# AVR28ZIF.net
KiCad netlist of a schematic drawn in EAGLE
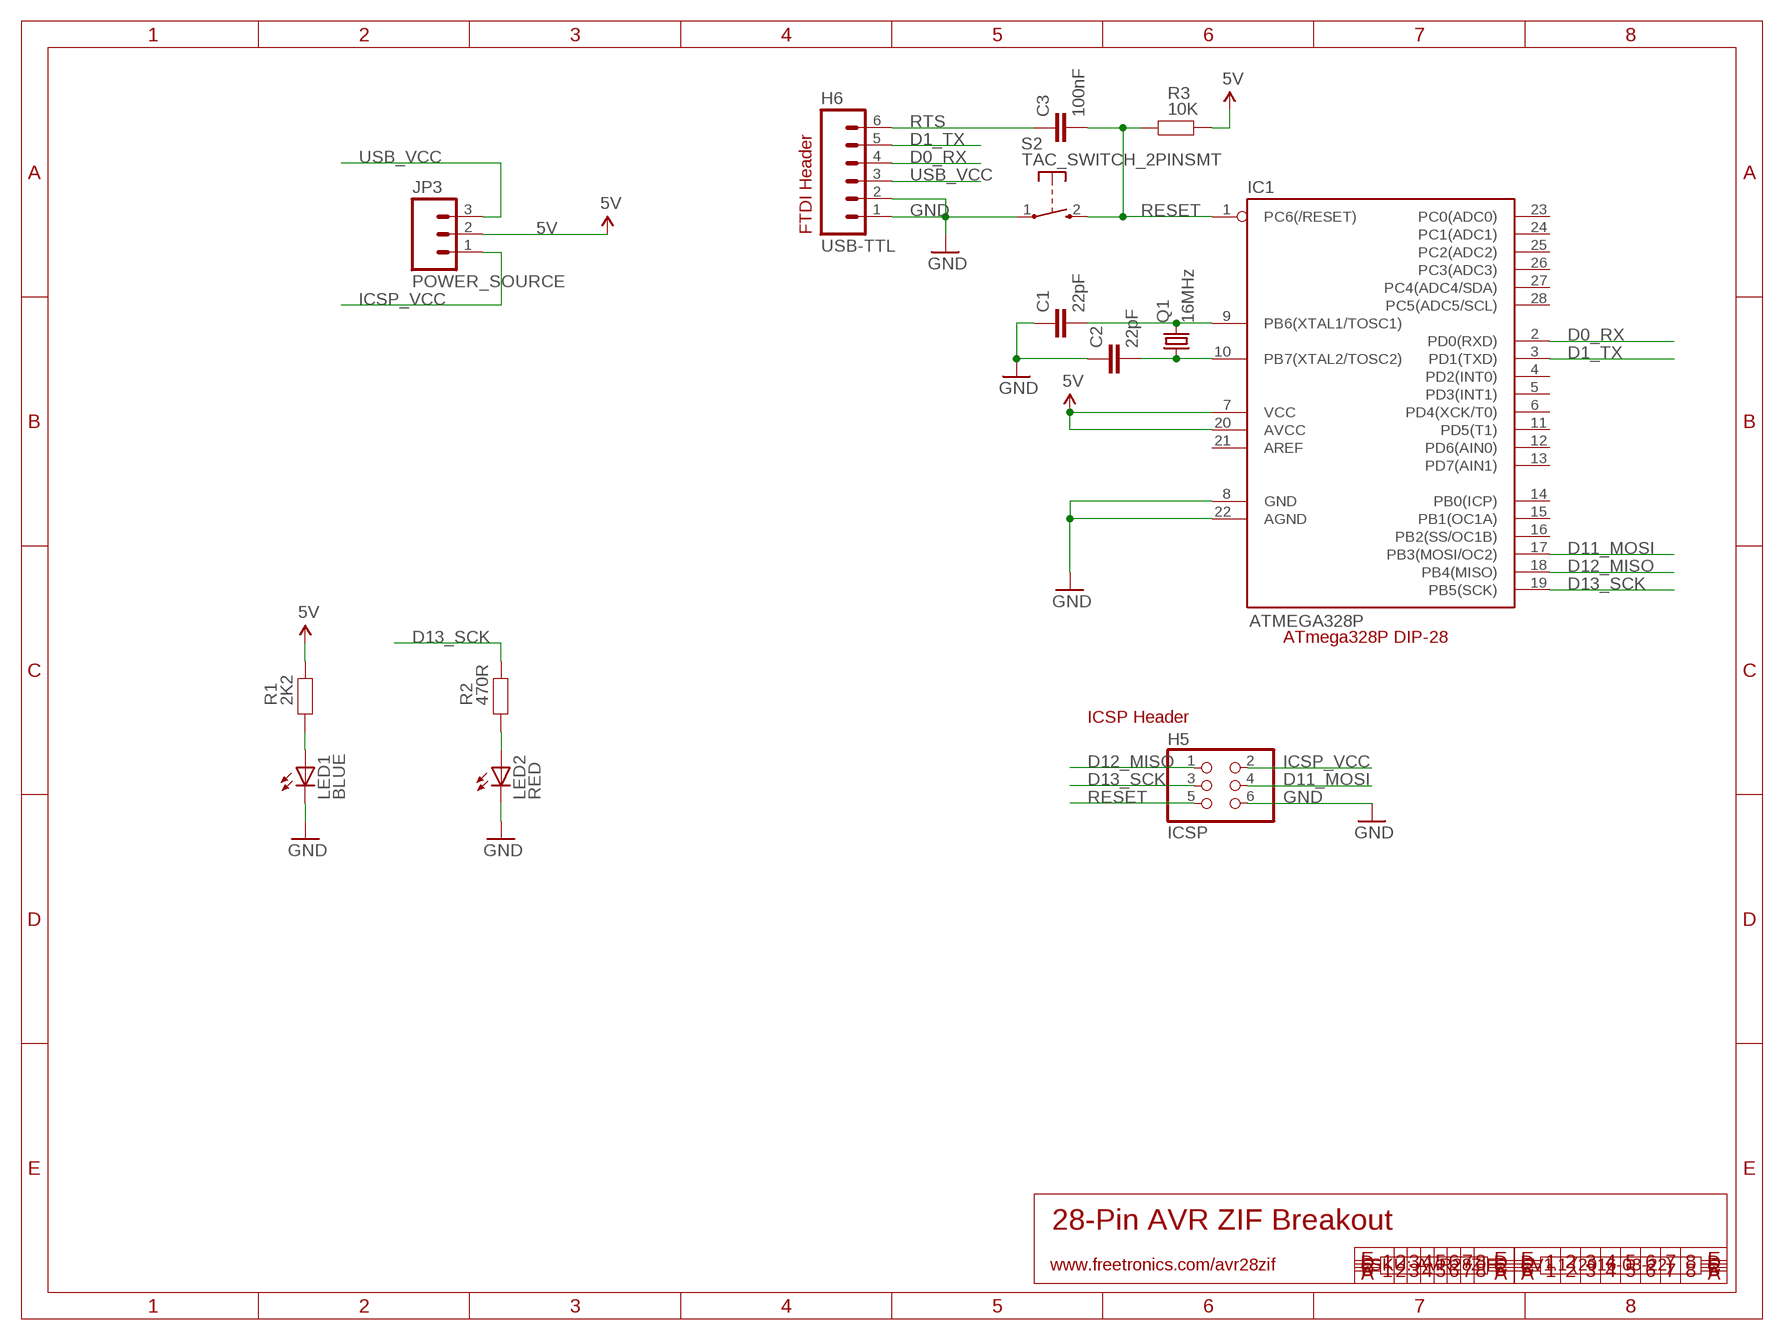
[diagram p0: schematic, sheet 1]

(export (version "E")
  (design (tool "Eeschema 10.0.6"))
  (components
    (comp (ref "C1")
      (value "22pF")
      (footprint "eagle-import:0603")
      (libsource (lib "eagle-import") (part "CAP0603"))
    )
    (comp (ref "C2")
      (value "22pF")
      (footprint "eagle-import:0603")
      (libsource (lib "eagle-import") (part "CAP0603"))
    )
    (comp (ref "C3")
      (value "100nF")
      (footprint "eagle-import:0603")
      (libsource (lib "eagle-import") (part "CAP0603"))
    )
    (comp (ref "H5")
      (value "ICSP")
      (footprint "eagle-import:2X03")
      (libsource (lib "eagle-import") (part "PINHD-2X3"))
    )
    (comp (ref "H6")
      (value "USB-TTL")
      (footprint "eagle-import:1X06")
      (libsource (lib "eagle-import") (part "M06SIP"))
    )
    (comp (ref "IC1")
      (value "ATMEGA328P")
      (footprint "eagle-import:DIL28-3-ZIF")
      (libsource (lib "eagle-import") (part "AVR-MEGA8-PZIF"))
    )
    (comp (ref "JP3")
      (value "POWER_SOURCE")
      (footprint "eagle-import:1X03")
      (libsource (lib "eagle-import") (part "M03PTH"))
    )
    (comp (ref "LED1")
      (value "BLUE")
      (footprint "eagle-import:LED-0603")
      (libsource (lib "eagle-import") (part "LED0603"))
    )
    (comp (ref "LED2")
      (value "RED")
      (footprint "eagle-import:LED-0603")
      (libsource (lib "eagle-import") (part "LED0603"))
    )
    (comp (ref "Q1")
      (value "16MHz")
      (footprint "eagle-import:HC49US")
      (libsource (lib "eagle-import") (part "CRYSTALHC49US"))
    )
    (comp (ref "R1")
      (value "2K2")
      (footprint "eagle-import:0603")
      (libsource (lib "eagle-import") (part "RESISTOR0603"))
    )
    (comp (ref "R2")
      (value "470R")
      (footprint "eagle-import:0603")
      (libsource (lib "eagle-import") (part "RESISTOR0603"))
    )
    (comp (ref "R3")
      (value "10K")
      (footprint "eagle-import:0603")
      (libsource (lib "eagle-import") (part "RESISTOR0603"))
    )
    (comp (ref "S2")
      (value "TAC_SWITCH_2PINSMT")
      (footprint "eagle-import:TACTILE_SWITCH_SMD_2PIN_TINY")
      (libsource (lib "eagle-import") (part "TAC_SWITCH_2PINSMT"))
    )
  )
  (nets
    (net (code "1") (name "/D0_RX") (class "Default")
      (node (ref "H6") (pin "4") (pinfunction "4_4") (pintype "passive"))
      (node (ref "IC1") (pin "2") (pinfunction "PD0(RXD)_2") (pintype "bidirectional"))
    )
    (net (code "2") (name "/D1_TX") (class "Default")
      (node (ref "H6") (pin "5") (pinfunction "5_5") (pintype "passive"))
      (node (ref "IC1") (pin "3") (pinfunction "PD1(TXD)_3") (pintype "bidirectional"))
    )
    (net (code "3") (name "/D11_MOSI") (class "Default")
      (node (ref "H5") (pin "4") (pinfunction "4_4") (pintype "passive"))
      (node (ref "IC1") (pin "17") (pinfunction "PB3(MOSI/OC2)_17") (pintype "bidirectional"))
    )
    (net (code "4") (name "/D12_MISO") (class "Default")
      (node (ref "H5") (pin "1") (pinfunction "1_1") (pintype "passive"))
      (node (ref "IC1") (pin "18") (pinfunction "PB4(MISO)_18") (pintype "bidirectional"))
    )
    (net (code "5") (name "/D13_SCK") (class "Default")
      (node (ref "H5") (pin "3") (pinfunction "3_3") (pintype "passive"))
      (node (ref "IC1") (pin "19") (pinfunction "PB5(SCK)_19") (pintype "bidirectional"))
      (node (ref "R2") (pin "2") (pinfunction "2_2") (pintype "passive"))
    )
    (net (code "6") (name "/ICSP_VCC") (class "Default")
      (node (ref "H5") (pin "2") (pinfunction "2_2") (pintype "passive"))
      (node (ref "JP3") (pin "1") (pinfunction "1_1") (pintype "passive"))
    )
    (net (code "7") (name "/RESET") (class "Default")
      (node (ref "C3") (pin "2") (pinfunction "2_2") (pintype "passive"))
      (node (ref "H5") (pin "5") (pinfunction "5_5") (pintype "passive"))
      (node (ref "IC1") (pin "1") (pinfunction "PC6(/RESET)_1") (pintype "bidirectional"))
      (node (ref "R3") (pin "1") (pinfunction "1_1") (pintype "passive"))
      (node (ref "S2") (pin "2") (pinfunction "S_2") (pintype "passive"))
    )
    (net (code "8") (name "/RTS") (class "Default")
      (node (ref "C3") (pin "1") (pinfunction "1_1") (pintype "passive"))
      (node (ref "H6") (pin "6") (pinfunction "6_6") (pintype "passive"))
    )
    (net (code "9") (name "/USB_VCC") (class "Default")
      (node (ref "H6") (pin "3") (pinfunction "3_3") (pintype "passive"))
      (node (ref "JP3") (pin "3") (pinfunction "3_3") (pintype "passive"))
    )
    (net (code "10") (name "5V") (class "Default")
      (node (ref "IC1") (pin "20") (pinfunction "AVCC_20") (pintype "bidirectional"))
      (node (ref "IC1") (pin "7") (pinfunction "VCC_7") (pintype "bidirectional"))
      (node (ref "JP3") (pin "2") (pinfunction "2_2") (pintype "passive"))
      (node (ref "R1") (pin "2") (pinfunction "2_2") (pintype "passive"))
      (node (ref "R3") (pin "2") (pinfunction "2_2") (pintype "passive"))
    )
    (net (code "11") (name "GND") (class "Default")
      (node (ref "C1") (pin "1") (pinfunction "1_1") (pintype "passive"))
      (node (ref "C2") (pin "1") (pinfunction "1_1") (pintype "passive"))
      (node (ref "H5") (pin "6") (pinfunction "6_6") (pintype "passive"))
      (node (ref "H6") (pin "1") (pinfunction "1_1") (pintype "passive"))
      (node (ref "H6") (pin "2") (pinfunction "2_2") (pintype "passive"))
      (node (ref "IC1") (pin "22") (pinfunction "AGND_22") (pintype "bidirectional"))
      (node (ref "IC1") (pin "8") (pinfunction "GND_8") (pintype "bidirectional"))
      (node (ref "LED1") (pin "C") (pinfunction "C_C") (pintype "passive"))
      (node (ref "LED2") (pin "C") (pinfunction "C_C") (pintype "passive"))
      (node (ref "S2") (pin "1") (pinfunction "P_1") (pintype "passive"))
    )
    (net (code "12") (name "Net-(IC1-PB6(XTAL1{slash}TOSC1))") (class "Default")
      (node (ref "C1") (pin "2") (pinfunction "2_2") (pintype "passive"))
      (node (ref "IC1") (pin "9") (pinfunction "PB6(XTAL1/TOSC1)_9") (pintype "bidirectional"))
      (node (ref "Q1") (pin "2") (pinfunction "2_2") (pintype "passive"))
    )
    (net (code "13") (name "Net-(IC1-PB7(XTAL2{slash}TOSC2))") (class "Default")
      (node (ref "C2") (pin "2") (pinfunction "2_2") (pintype "passive"))
      (node (ref "IC1") (pin "10") (pinfunction "PB7(XTAL2/TOSC2)_10") (pintype "bidirectional"))
      (node (ref "Q1") (pin "1") (pinfunction "1_1") (pintype "passive"))
    )
    (net (code "14") (name "Net-(LED1-PadA)") (class "Default")
      (node (ref "LED1") (pin "A") (pinfunction "A_A") (pintype "passive"))
      (node (ref "R1") (pin "1") (pinfunction "1_1") (pintype "passive"))
    )
    (net (code "15") (name "Net-(LED2-PadA)") (class "Default")
      (node (ref "LED2") (pin "A") (pinfunction "A_A") (pintype "passive"))
      (node (ref "R2") (pin "1") (pinfunction "1_1") (pintype "passive"))
    )
    (net (code "16") (name "unconnected-(IC1-AREF-Pad21)") (class "Default")
      (node (ref "IC1") (pin "21") (pinfunction "AREF_21") (pintype "bidirectional"))
    )
    (net (code "17") (name "unconnected-(IC1-PB0(ICP)-Pad14)") (class "Default")
      (node (ref "IC1") (pin "14") (pinfunction "PB0(ICP)_14") (pintype "bidirectional"))
    )
    (net (code "18") (name "unconnected-(IC1-PB1(OC1A)-Pad15)") (class "Default")
      (node (ref "IC1") (pin "15") (pinfunction "PB1(OC1A)_15") (pintype "bidirectional"))
    )
    (net (code "19") (name "unconnected-(IC1-PB2(SS{slash}OC1B)-Pad16)") (class "Default")
      (node (ref "IC1") (pin "16") (pinfunction "PB2(SS/OC1B)_16") (pintype "bidirectional"))
    )
    (net (code "20") (name "unconnected-(IC1-PC0(ADC0)-Pad23)") (class "Default")
      (node (ref "IC1") (pin "23") (pinfunction "PC0(ADC0)_23") (pintype "bidirectional"))
    )
    (net (code "21") (name "unconnected-(IC1-PC1(ADC1)-Pad24)") (class "Default")
      (node (ref "IC1") (pin "24") (pinfunction "PC1(ADC1)_24") (pintype "bidirectional"))
    )
    (net (code "22") (name "unconnected-(IC1-PC2(ADC2)-Pad25)") (class "Default")
      (node (ref "IC1") (pin "25") (pinfunction "PC2(ADC2)_25") (pintype "bidirectional"))
    )
    (net (code "23") (name "unconnected-(IC1-PC3(ADC3)-Pad26)") (class "Default")
      (node (ref "IC1") (pin "26") (pinfunction "PC3(ADC3)_26") (pintype "bidirectional"))
    )
    (net (code "24") (name "unconnected-(IC1-PC4(ADC4{slash}SDA)-Pad27)") (class "Default")
      (node (ref "IC1") (pin "27") (pinfunction "PC4(ADC4/SDA)_27") (pintype "bidirectional"))
    )
    (net (code "25") (name "unconnected-(IC1-PC5(ADC5{slash}SCL)-Pad28)") (class "Default")
      (node (ref "IC1") (pin "28") (pinfunction "PC5(ADC5/SCL)_28") (pintype "bidirectional"))
    )
    (net (code "26") (name "unconnected-(IC1-PD2(INT0)-Pad4)") (class "Default")
      (node (ref "IC1") (pin "4") (pinfunction "PD2(INT0)_4") (pintype "bidirectional"))
    )
    (net (code "27") (name "unconnected-(IC1-PD3(INT1)-Pad5)") (class "Default")
      (node (ref "IC1") (pin "5") (pinfunction "PD3(INT1)_5") (pintype "bidirectional"))
    )
    (net (code "28") (name "unconnected-(IC1-PD4(XCK{slash}T0)-Pad6)") (class "Default")
      (node (ref "IC1") (pin "6") (pinfunction "PD4(XCK/T0)_6") (pintype "bidirectional"))
    )
    (net (code "29") (name "unconnected-(IC1-PD5(T1)-Pad11)") (class "Default")
      (node (ref "IC1") (pin "11") (pinfunction "PD5(T1)_11") (pintype "bidirectional"))
    )
    (net (code "30") (name "unconnected-(IC1-PD6(AIN0)-Pad12)") (class "Default")
      (node (ref "IC1") (pin "12") (pinfunction "PD6(AIN0)_12") (pintype "bidirectional"))
    )
    (net (code "31") (name "unconnected-(IC1-PD7(AIN1)-Pad13)") (class "Default")
      (node (ref "IC1") (pin "13") (pinfunction "PD7(AIN1)_13") (pintype "bidirectional"))
    )
  )
)
